# Esquem_tico.net
KiCad netlist of a schematic drawn in EAGLE
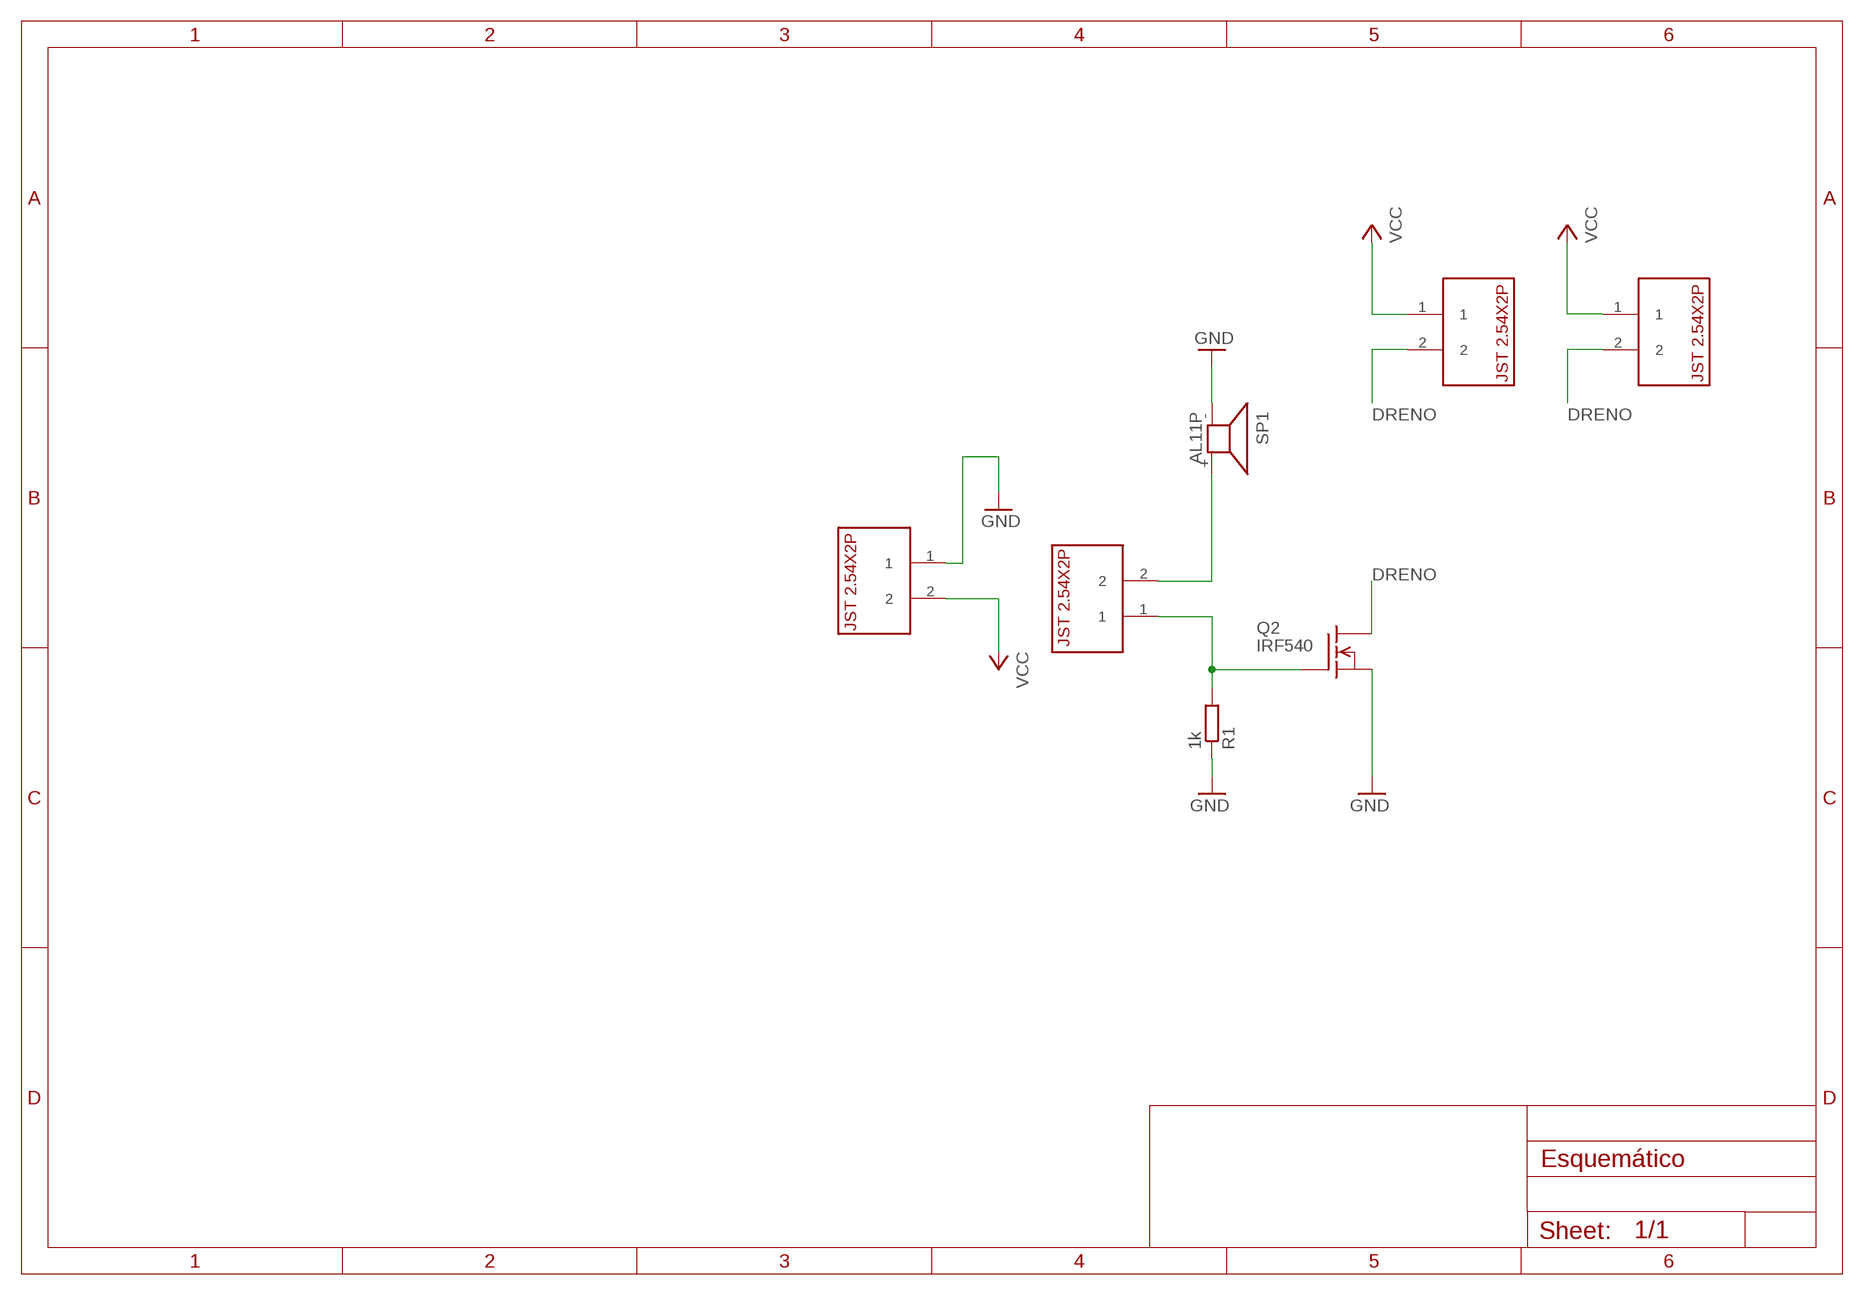
[diagram p0: schematic, sheet 1]

(export (version "E")
  (design (tool "Eeschema 10.0.6"))
  (components
    (comp (ref "Q2")
      (value "IRF540")
      (footprint "eagle-import:TO220")
      (libsource (lib "eagle-import") (part "IRF540"))
    )
    (comp (ref "R1")
      (value "1k")
      (footprint "eagle-import:0204_7")
      (libsource (lib "eagle-import") (part "R-EU_0204/7"))
    )
    (comp (ref "SP1")
      (value "AL11P")
      (footprint "eagle-import:AL11P")
      (libsource (lib "eagle-import") (part "AL11P"))
    )
    (comp (ref "U$1")
      (value "JST2.54X2P")
      (footprint "eagle-import:JST2.54X2P_FOOTPRINT")
      (libsource (lib "eagle-import") (part "JST2.54X2P"))
    )
    (comp (ref "U$2")
      (value "JST2.54X2P")
      (footprint "eagle-import:JST2.54X2P_FOOTPRINT")
      (libsource (lib "eagle-import") (part "JST2.54X2P"))
    )
    (comp (ref "U$3")
      (value "JST2.54X2P")
      (footprint "eagle-import:JST2.54X2P_FOOTPRINT")
      (libsource (lib "eagle-import") (part "JST2.54X2P"))
    )
    (comp (ref "U$4")
      (value "JST2.54X2P")
      (footprint "eagle-import:JST2.54X2P_FOOTPRINT")
      (libsource (lib "eagle-import") (part "JST2.54X2P"))
    )
  )
  (nets
    (net (code "1") (name "/DRENO") (class "Default")
      (node (ref "Q2") (pin "2") (pinfunction "D_2") (pintype "passive"))
      (node (ref "U$2") (pin "2") (pinfunction "2_2") (pintype "bidirectional"))
      (node (ref "U$3") (pin "2") (pinfunction "2_2") (pintype "bidirectional"))
    )
    (net (code "2") (name "GND") (class "Default")
      (node (ref "Q2") (pin "3") (pinfunction "S_3") (pintype "passive"))
      (node (ref "R1") (pin "1") (pinfunction "1_1") (pintype "passive"))
      (node (ref "SP1") (pin "-") (pinfunction "1_-") (pintype "passive"))
      (node (ref "U$4") (pin "1") (pinfunction "1_1") (pintype "bidirectional"))
    )
    (net (code "3") (name "Net-(Q2-G)") (class "Default")
      (node (ref "Q2") (pin "1") (pinfunction "G_1") (pintype "passive"))
      (node (ref "R1") (pin "2") (pinfunction "2_2") (pintype "passive"))
      (node (ref "U$1") (pin "1") (pinfunction "1_1") (pintype "bidirectional"))
    )
    (net (code "4") (name "Net-(SP1-2)") (class "Default")
      (node (ref "SP1") (pin "+") (pinfunction "2_+") (pintype "passive"))
      (node (ref "U$1") (pin "2") (pinfunction "2_2") (pintype "bidirectional"))
    )
    (net (code "5") (name "VCC") (class "Default")
      (node (ref "U$2") (pin "1") (pinfunction "1_1") (pintype "bidirectional"))
      (node (ref "U$3") (pin "1") (pinfunction "1_1") (pintype "bidirectional"))
      (node (ref "U$4") (pin "2") (pinfunction "2_2") (pintype "bidirectional"))
    )
  )
)
